# DYBoard_Feeder.net
KiCad netlist of a schematic drawn in Altium Designer
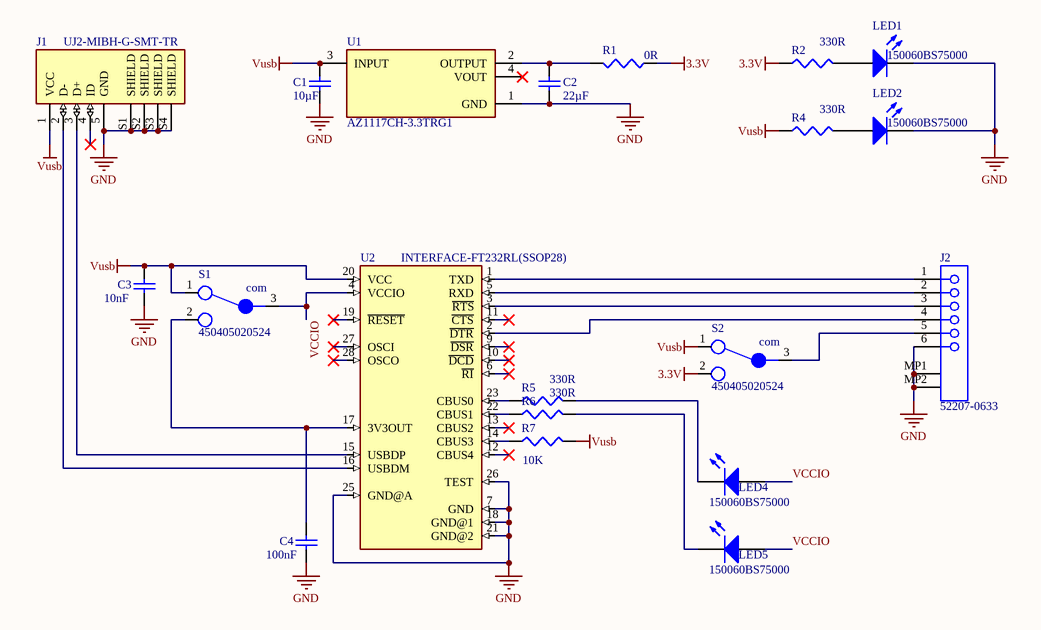
[diagram p0: DYBoard_Feeder.SchDoc]

(export (version "E")
  (design (tool "Eeschema 10.0.6"))
  (components
    (comp (ref "C1")
      (value "10µF")
      (footprint "1608[0603]")
      (description "Capacitor (Semiconductor SIM Model)")
      (fields (field (name "Comment") "Cap Semi") (field (name "PUBLISHER") "Altium Limited"))
      (libsource (lib "Miscellaneous Devices") (part "Cap Semi"))
    )
    (comp (ref "C2")
      (value "22µF")
      (footprint "1608[0603]")
      (description "Capacitor (Semiconductor SIM Model)")
      (fields (field (name "Comment") "Cap Semi") (field (name "PUBLISHER") "Altium Limited"))
      (libsource (lib "Miscellaneous Devices") (part "Cap Semi"))
    )
    (comp (ref "C3")
      (value "10nF")
      (footprint "1608[0603]")
      (description "Capacitor (Semiconductor SIM Model)")
      (fields (field (name "Comment") "Cap Semi") (field (name "PUBLISHER") "Altium Limited"))
      (libsource (lib "Miscellaneous Devices") (part "Cap Semi"))
    )
    (comp (ref "C4")
      (value "100nF")
      (footprint "1608[0603]")
      (description "Capacitor (Semiconductor SIM Model)")
      (fields (field (name "Comment") "Cap Semi") (field (name "PUBLISHER") "Altium Limited"))
      (libsource (lib "Miscellaneous Devices") (part "Cap Semi"))
    )
    (comp (ref "J1")
      (value "UJ2-MIBH-G-SMT-TR")
      (footprint "CUI_UJ2-MIBH-G-SMT-TR")
      (description "Micro B, USB 2.0, 1.8 A, Right Angle, Surface Mount (SMT), USB Receptacle")
      (fields (field (name "MF") "CUI Devices"))
      (libsource (lib "UJ2-MIBH-G-SMT-TR") (part "UJ2-MIBH-G-SMT-TR"))
    )
    (comp (ref "J2")
      (value "52207-0633")
      (footprint "MOLX-52207-0633")
      (fields (field (name "MANUFACTURER") "Molex"))
      (libsource (lib "Altium Content Vault") (part "MOLX-52207-0633"))
    )
    (comp (ref "LED1")
      (value "150060BS75000")
      (footprint "0603_A")
      (description "SMD mono-color Chip LED, WL-SMCW, Blue")
      (fields (field (name "MANUFACTURER") "Wuerth Elektronik"))
      (libsource (lib "Altium Content Vault") (part "WE-LED_K1A2-2"))
    )
    (comp (ref "LED2")
      (value "150060BS75000")
      (footprint "0603_A")
      (description "SMD mono-color Chip LED, WL-SMCW, Blue")
      (fields (field (name "MANUFACTURER") "Wuerth Elektronik"))
      (libsource (lib "Altium Content Vault") (part "WE-LED_K1A2-2"))
    )
    (comp (ref "LED4")
      (value "150060BS75000")
      (footprint "0603_A")
      (description "SMD mono-color Chip LED, WL-SMCW, Blue")
      (fields (field (name "MANUFACTURER") "Wuerth Elektronik"))
      (libsource (lib "Altium Content Vault") (part "WE-LED_K1A2-2"))
    )
    (comp (ref "LED5")
      (value "150060BS75000")
      (footprint "0603_A")
      (description "SMD mono-color Chip LED, WL-SMCW, Blue")
      (fields (field (name "MANUFACTURER") "Wuerth Elektronik"))
      (libsource (lib "Altium Content Vault") (part "WE-LED_K1A2-2"))
    )
    (comp (ref "R1")
      (value "0R")
      (footprint "J1-0603")
      (description "Resistor")
      (fields (field (name "Comment") "Res3") (field (name "PUBLISHER") "Altium Limited"))
      (libsource (lib "Miscellaneous Devices") (part "Res3"))
    )
    (comp (ref "R2")
      (value "330R")
      (footprint "J1-0603")
      (description "Resistor")
      (fields (field (name "Comment") "Res3") (field (name "PUBLISHER") "Altium Limited"))
      (libsource (lib "Miscellaneous Devices") (part "Res3"))
    )
    (comp (ref "R4")
      (value "330R")
      (footprint "J1-0603")
      (description "Resistor")
      (fields (field (name "Comment") "Res3") (field (name "PUBLISHER") "Altium Limited"))
      (libsource (lib "Miscellaneous Devices") (part "Res3"))
    )
    (comp (ref "R5")
      (value "330R")
      (footprint "J1-0603")
      (description "Resistor")
      (fields (field (name "Comment") "Res3") (field (name "PUBLISHER") "Altium Limited"))
      (libsource (lib "Miscellaneous Devices") (part "Res3"))
    )
    (comp (ref "R6")
      (value "330R")
      (footprint "J1-0603")
      (description "Resistor")
      (fields (field (name "Comment") "Res3") (field (name "PUBLISHER") "Altium Limited"))
      (libsource (lib "Miscellaneous Devices") (part "Res3"))
    )
    (comp (ref "R7")
      (value "10K")
      (footprint "J1-0603")
      (description "Resistor")
      (fields (field (name "Comment") "Res3") (field (name "PUBLISHER") "Altium Limited"))
      (libsource (lib "Miscellaneous Devices") (part "Res3"))
    )
    (comp (ref "S1")
      (value "450405020524")
      (footprint "450405020524")
      (description "SMT 8.7 X 3.0 MM MINI SLIDE SWIT")
      (fields (field (name "MF") "WÃ¼rth Elektronik"))
      (libsource (lib "450405020524") (part "450405020524"))
    )
    (comp (ref "S2")
      (value "450405020524")
      (footprint "450405020524")
      (description "SMT 8.7 X 3.0 MM MINI SLIDE SWIT")
      (fields (field (name "MF") "WÃ¼rth Elektronik"))
      (libsource (lib "450405020524") (part "450405020524"))
    )
    (comp (ref "U1")
      (value "AZ1117CH-3.3TRG1")
      (footprint "FP-SOT223-MFG")
      (description "IC REG LINEAR 3.3V 800MA SOT223")
      (libsource (lib "Altium Content Vault") (part "bae10108a039f7d2bfd31a2f0f6c252"))
    )
    (comp (ref "U2")
      (value "INTERFACE-FT232RL(SSOP28)")
      (footprint "SSOP28-0.65-10.2X5.2MM")
      (description "USB Bridge, USB to UART USB 2.0 UART Interface 28-SSOP")
      (fields (field (name "MP") "FT232RL") (field (name "MF") "FTDI, Future"))
      (libsource (lib "INTERFACE-FT232RL_SSOP28_") (part "INTERFACE-FT232RL(SSOP28)"))
    )
  )
  (nets
    (net (code "1") (name "/VCCIO") (class "Default")
      (node (ref "LED4") (pin "2") (pinfunction "A_2") (pintype "passive"))
      (node (ref "LED5") (pin "2") (pinfunction "A_2") (pintype "passive"))
      (node (ref "S1") (pin "3") (pinfunction "3_3") (pintype "passive"))
      (node (ref "U2") (pin "4") (pinfunction "VCCIO_4") (pintype "input"))
    )
    (net (code "2") (name "3.3V") (class "Default")
      (node (ref "R1") (pin "1") (pinfunction "1_1") (pintype "passive"))
      (node (ref "R2") (pin "1") (pinfunction "1_1") (pintype "passive"))
      (node (ref "S2") (pin "2") (pinfunction "2_2") (pintype "passive"))
    )
    (net (code "3") (name "GND") (class "Default")
      (node (ref "C1") (pin "1") (pinfunction "1_1") (pintype "passive"))
      (node (ref "C2") (pin "1") (pinfunction "1_1") (pintype "passive"))
      (node (ref "C3") (pin "1") (pinfunction "1_1") (pintype "passive"))
      (node (ref "C4") (pin "1") (pinfunction "1_1") (pintype "passive"))
      (node (ref "J1") (pin "5") (pinfunction "GND_5") (pintype "power_in"))
      (node (ref "J1") (pin "S1") (pinfunction "SHIELD_S1") (pintype "passive"))
      (node (ref "J1") (pin "S2") (pinfunction "SHIELD_S2") (pintype "passive"))
      (node (ref "J1") (pin "S3") (pinfunction "SHIELD_S3") (pintype "passive"))
      (node (ref "J1") (pin "S4") (pinfunction "SHIELD_S4") (pintype "passive"))
      (node (ref "J2") (pin "6") (pinfunction "6_6") (pintype "passive"))
      (node (ref "J2") (pin "MP1") (pinfunction "MP1_MP1") (pintype "passive"))
      (node (ref "J2") (pin "MP2") (pinfunction "MP2_MP2") (pintype "passive"))
      (node (ref "LED1") (pin "1") (pinfunction "K_1") (pintype "passive"))
      (node (ref "LED2") (pin "1") (pinfunction "K_1") (pintype "passive"))
      (node (ref "U1") (pin "1") (pinfunction "GND_1") (pintype "power_in"))
      (node (ref "U2") (pin "18") (pinfunction "GND@1_18") (pintype "input"))
      (node (ref "U2") (pin "21") (pinfunction "GND@2_21") (pintype "input"))
      (node (ref "U2") (pin "25") (pinfunction "GND@A_25") (pintype "input"))
      (node (ref "U2") (pin "26") (pinfunction "TEST_26") (pintype "input"))
      (node (ref "U2") (pin "7") (pinfunction "GND_7") (pintype "input"))
    )
    (net (code "4") (name "Net-(J1-D+)") (class "Default")
      (node (ref "J1") (pin "3") (pinfunction "D+_3") (pintype "bidirectional"))
      (node (ref "U2") (pin "15") (pinfunction "USBDP_15") (pintype "input"))
    )
    (net (code "5") (name "Net-(J1-D-)") (class "Default")
      (node (ref "J1") (pin "2") (pinfunction "D-_2") (pintype "bidirectional"))
      (node (ref "U2") (pin "16") (pinfunction "USBDM_16") (pintype "input"))
    )
    (net (code "6") (name "Net-(J2-Pad5)") (class "Default")
      (node (ref "J2") (pin "5") (pinfunction "5_5") (pintype "passive"))
      (node (ref "S2") (pin "3") (pinfunction "3_3") (pintype "passive"))
    )
    (net (code "7") (name "Net-(LED1-A)") (class "Default")
      (node (ref "LED1") (pin "2") (pinfunction "A_2") (pintype "passive"))
      (node (ref "R2") (pin "2") (pinfunction "2_2") (pintype "passive"))
    )
    (net (code "8") (name "Net-(LED2-A)") (class "Default")
      (node (ref "LED2") (pin "2") (pinfunction "A_2") (pintype "passive"))
      (node (ref "R4") (pin "2") (pinfunction "2_2") (pintype "passive"))
    )
    (net (code "9") (name "Net-(LED4-K)") (class "Default")
      (node (ref "LED4") (pin "1") (pinfunction "K_1") (pintype "passive"))
      (node (ref "R5") (pin "2") (pinfunction "2_2") (pintype "passive"))
    )
    (net (code "10") (name "Net-(LED5-K)") (class "Default")
      (node (ref "LED5") (pin "1") (pinfunction "K_1") (pintype "passive"))
      (node (ref "R6") (pin "2") (pinfunction "2_2") (pintype "passive"))
    )
    (net (code "11") (name "Net-(U1-OUTPUT)") (class "Default")
      (node (ref "C2") (pin "2") (pinfunction "2_2") (pintype "passive"))
      (node (ref "R1") (pin "2") (pinfunction "2_2") (pintype "passive"))
      (node (ref "U1") (pin "2") (pinfunction "OUTPUT_2") (pintype "power_in"))
    )
    (net (code "12") (name "Net-(U2-3V3OUT)") (class "Default")
      (node (ref "C4") (pin "2") (pinfunction "2_2") (pintype "passive"))
      (node (ref "S1") (pin "2") (pinfunction "2_2") (pintype "passive"))
      (node (ref "U2") (pin "17") (pinfunction "3V3OUT_17") (pintype "input"))
    )
    (net (code "13") (name "Net-(U2-CBUS0)") (class "Default")
      (node (ref "R5") (pin "1") (pinfunction "1_1") (pintype "passive"))
      (node (ref "U2") (pin "23") (pinfunction "CBUS0_23") (pintype "input"))
    )
    (net (code "14") (name "Net-(U2-CBUS1)") (class "Default")
      (node (ref "R6") (pin "1") (pinfunction "1_1") (pintype "passive"))
      (node (ref "U2") (pin "22") (pinfunction "CBUS1_22") (pintype "input"))
    )
    (net (code "15") (name "Net-(U2-CBUS3)") (class "Default")
      (node (ref "R7") (pin "1") (pinfunction "1_1") (pintype "passive"))
      (node (ref "U2") (pin "14") (pinfunction "CBUS3_14") (pintype "input"))
    )
    (net (code "16") (name "Net-(U2-RXD)") (class "Default")
      (node (ref "J2") (pin "2") (pinfunction "2_2") (pintype "passive"))
      (node (ref "U2") (pin "5") (pinfunction "RXD_5") (pintype "input"))
    )
    (net (code "17") (name "Net-(U2-TXD)") (class "Default")
      (node (ref "J2") (pin "1") (pinfunction "1_1") (pintype "passive"))
      (node (ref "U2") (pin "1") (pinfunction "TXD_1") (pintype "input"))
    )
    (net (code "18") (name "Net-(U2-~{DTR})") (class "Default")
      (node (ref "J2") (pin "4") (pinfunction "4_4") (pintype "passive"))
      (node (ref "U2") (pin "2") (pinfunction "~{DTR}_2") (pintype "input"))
    )
    (net (code "19") (name "Net-(U2-~{RTS})") (class "Default")
      (node (ref "J2") (pin "3") (pinfunction "3_3") (pintype "passive"))
      (node (ref "U2") (pin "3") (pinfunction "~{RTS}_3") (pintype "input"))
    )
    (net (code "20") (name "Vusb") (class "Default")
      (node (ref "C1") (pin "2") (pinfunction "2_2") (pintype "passive"))
      (node (ref "C3") (pin "2") (pinfunction "2_2") (pintype "passive"))
      (node (ref "J1") (pin "1") (pinfunction "VCC_1") (pintype "power_in"))
      (node (ref "R4") (pin "1") (pinfunction "1_1") (pintype "passive"))
      (node (ref "R7") (pin "2") (pinfunction "2_2") (pintype "passive"))
      (node (ref "S1") (pin "1") (pinfunction "1_1") (pintype "passive"))
      (node (ref "S2") (pin "1") (pinfunction "1_1") (pintype "passive"))
      (node (ref "U1") (pin "3") (pinfunction "INPUT_3") (pintype "power_in"))
      (node (ref "U2") (pin "20") (pinfunction "VCC_20") (pintype "input"))
    )
    (net (code "21") (name "unconnected-(J1-ID-Pad4)") (class "Default")
      (node (ref "J1") (pin "4") (pinfunction "ID_4") (pintype "bidirectional+no_connect"))
    )
    (net (code "22") (name "unconnected-(U1-VOUT-Pad4)") (class "Default")
      (node (ref "U1") (pin "4") (pinfunction "VOUT_4") (pintype "power_in+no_connect"))
    )
    (net (code "23") (name "unconnected-(U2-CBUS2-Pad13)") (class "Default")
      (node (ref "U2") (pin "13") (pinfunction "CBUS2_13") (pintype "input+no_connect"))
    )
    (net (code "24") (name "unconnected-(U2-CBUS4-Pad12)") (class "Default")
      (node (ref "U2") (pin "12") (pinfunction "CBUS4_12") (pintype "input+no_connect"))
    )
    (net (code "25") (name "unconnected-(U2-OSCI-Pad27)") (class "Default")
      (node (ref "U2") (pin "27") (pinfunction "OSCI_27") (pintype "input+no_connect"))
    )
    (net (code "26") (name "unconnected-(U2-OSCO-Pad28)") (class "Default")
      (node (ref "U2") (pin "28") (pinfunction "OSCO_28") (pintype "input+no_connect"))
    )
    (net (code "27") (name "unconnected-(U2-~{CTS}-Pad11)") (class "Default")
      (node (ref "U2") (pin "11") (pinfunction "~{CTS}_11") (pintype "input+no_connect"))
    )
    (net (code "28") (name "unconnected-(U2-~{DCD}-Pad10)") (class "Default")
      (node (ref "U2") (pin "10") (pinfunction "~{DCD}_10") (pintype "input+no_connect"))
    )
    (net (code "29") (name "unconnected-(U2-~{DSR}-Pad9)") (class "Default")
      (node (ref "U2") (pin "9") (pinfunction "~{DSR}_9") (pintype "input+no_connect"))
    )
    (net (code "30") (name "unconnected-(U2-~{RESET}-Pad19)") (class "Default")
      (node (ref "U2") (pin "19") (pinfunction "~{RESET}_19") (pintype "input+no_connect"))
    )
    (net (code "31") (name "unconnected-(U2-~{RI}-Pad6)") (class "Default")
      (node (ref "U2") (pin "6") (pinfunction "~{RI}_6") (pintype "input+no_connect"))
    )
  )
)
